# SH5_-_MICROCONTROLLER.net
KiCad netlist of a schematic drawn in Altium Designer
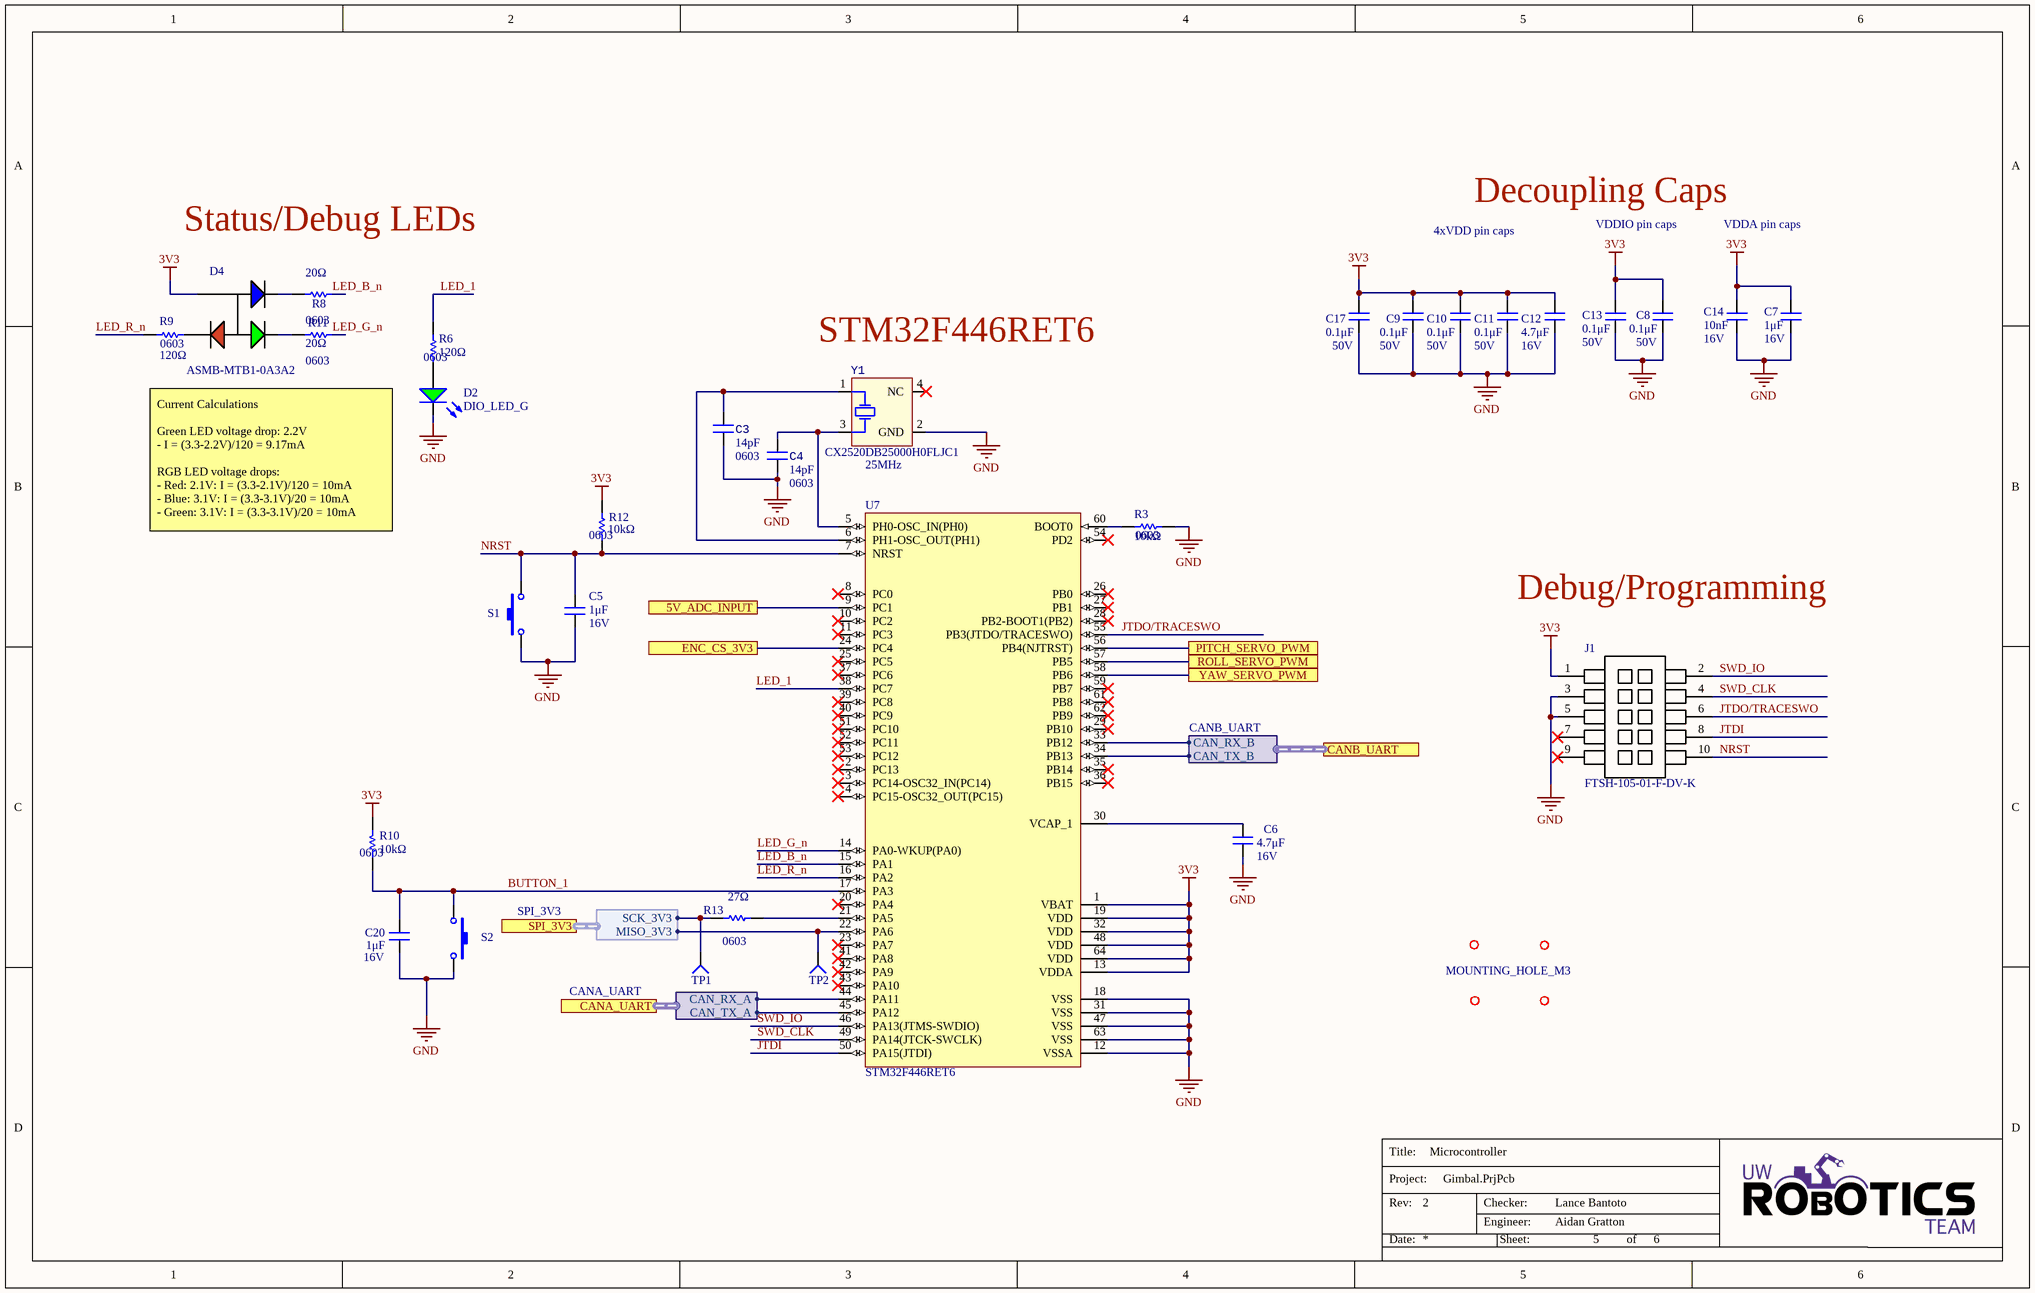
[diagram p0: SH5 - MICROCONTROLLER.SchDoc]

(export (version "E")
  (design (tool "Eeschema 10.0.6"))
  (components
    (comp (ref "C3")
      (value "14pF")
      (footprint "CAP0603")
      (description "CAP CER 14PF 50V C0G/NP0 0603")
      (fields (field (name "PACKAGE/FOOTPRINT") "0603") (field (name "Comment") "CAP_14pF_50V_0603"))
      (libsource (lib "UWRT_Schematic_Library_2020") (part "CAP_14pF_50V_0603"))
    )
    (comp (ref "C4")
      (value "14pF")
      (footprint "CAP0603")
      (description "CAP CER 14PF 50V C0G/NP0 0603")
      (fields (field (name "PACKAGE/FOOTPRINT") "0603") (field (name "Comment") "CAP_14pF_50V_0603"))
      (libsource (lib "UWRT_Schematic_Library_2020") (part "CAP_14pF_50V_0603"))
    )
    (comp (ref "C5")
      (value "1μF")
      (footprint "CAP2012")
      (description "CAP CER 1UF 16V X7R 0805")
      (fields
        (field (name "TOLERANCE") "10%")
        (field (name "VOLTAGE RATING") "16V")
        (field (name "Comment") "CAP_1uF_16V_0805")
      )
      (libsource (lib "UWRT_Schematic_Library_2020") (part "CAP_1uF_16V_0805"))
    )
    (comp (ref "C6")
      (value "4.7μF")
      (footprint "CAP2012")
      (description "CAP CER 4.7UF 16V X5R 0805")
      (fields
        (field (name "VOLTAGE RATING") "16V")
        (field (name "LCSC PART #") "C1779")
        (field (name "Comment") "CAP_4.7uF_16V_0805")
      )
      (libsource (lib "UWRT_Schematic_Library_2020") (part "CAP_4.7uF_16V_0805"))
    )
    (comp (ref "C7")
      (value "1μF")
      (footprint "CAP0603")
      (description "CAP CER 1UF 16V Y5V 0603")
      (fields
        (field (name "VOLTAGE RATING") "16V")
        (field (name "MANUFACTURER PART NUMBER") "CC0603ZRY5V7BB105")
        (field (name "Comment") "CAP_1uF_16V_0603")
      )
      (libsource (lib "UWRT_Schematic_Library_2020") (part "CAP_1uF_16V_0603"))
    )
    (comp (ref "C8")
      (value "0.1μF")
      (footprint "CAP0603")
      (description "CAP CER 0.1UF 50V X7R 0603")
      (fields (field (name "VOLTAGE RATING") "50V") (field (name "Comment") "CAP_0.1uF_50V_0603"))
      (libsource (lib "UWRT_Schematic_Library_2020") (part "CAP_0.1uF_50V_0603"))
    )
    (comp (ref "C9")
      (value "0.1μF")
      (footprint "CAP0603")
      (description "CAP CER 0.1UF 50V X7R 0603")
      (fields (field (name "VOLTAGE RATING") "50V") (field (name "Comment") "CAP_0.1uF_50V_0603"))
      (libsource (lib "UWRT_Schematic_Library_2020") (part "CAP_0.1uF_50V_0603"))
    )
    (comp (ref "C10")
      (value "0.1μF")
      (footprint "CAP0603")
      (description "CAP CER 0.1UF 50V X7R 0603")
      (fields (field (name "VOLTAGE RATING") "50V") (field (name "Comment") "CAP_0.1uF_50V_0603"))
      (libsource (lib "UWRT_Schematic_Library_2020") (part "CAP_0.1uF_50V_0603"))
    )
    (comp (ref "C11")
      (value "0.1μF")
      (footprint "CAP0603")
      (description "CAP CER 0.1UF 50V X7R 0603")
      (fields (field (name "VOLTAGE RATING") "50V") (field (name "Comment") "CAP_0.1uF_50V_0603"))
      (libsource (lib "UWRT_Schematic_Library_2020") (part "CAP_0.1uF_50V_0603"))
    )
    (comp (ref "C12")
      (value "4.7μF")
      (footprint "CAP2012")
      (description "CAP CER 4.7UF 16V X5R 0805")
      (fields
        (field (name "VOLTAGE RATING") "16V")
        (field (name "LCSC PART #") "C1779")
        (field (name "Comment") "CAP_4.7uF_16V_0805")
      )
      (libsource (lib "UWRT_Schematic_Library_2020") (part "CAP_4.7uF_16V_0805"))
    )
    (comp (ref "C13")
      (value "0.1μF")
      (footprint "CAP0603")
      (description "CAP CER 0.1UF 50V X7R 0603")
      (fields (field (name "VOLTAGE RATING") "50V") (field (name "Comment") "CAP_0.1uF_50V_0603"))
      (libsource (lib "UWRT_Schematic_Library_2020") (part "CAP_0.1uF_50V_0603"))
    )
    (comp (ref "C14")
      (value "10nF")
      (footprint "CAP0603")
      (description "CAP CER 10000PF 16V X7R 0603")
      (fields (field (name "VOLTAGE RATING") "16V") (field (name "Comment") "CAP_10nF_0603"))
      (libsource (lib "UWRT_Schematic_Library_2020") (part "CAP_10nF_0603"))
    )
    (comp (ref "C17")
      (value "0.1μF")
      (footprint "CAP0603")
      (description "CAP CER 0.1UF 50V X7R 0603")
      (fields (field (name "VOLTAGE RATING") "50V") (field (name "Comment") "CAP_0.1uF_50V_0603"))
      (libsource (lib "UWRT_Schematic_Library_2020") (part "CAP_0.1uF_50V_0603"))
    )
    (comp (ref "C20")
      (value "1μF")
      (footprint "CAP2012")
      (description "CAP CER 1UF 16V X7R 0805")
      (fields
        (field (name "TOLERANCE") "10%")
        (field (name "VOLTAGE RATING") "16V")
        (field (name "Comment") "CAP_1uF_16V_0805")
      )
      (libsource (lib "UWRT_Schematic_Library_2020") (part "CAP_1uF_16V_0805"))
    )
    (comp (ref "D2")
      (value "DIO_LED_G")
      (footprint "LED_0805_GREEN")
      (description "LED GREEN DIFFUSED 0805 SMD")
      (libsource (lib "UWRT_Schematic_Library_2020") (part "DIO_LED_G"))
    )
    (comp (ref "D4")
      (value "LED_RGB")
      (footprint "LED_RGB")
      (description "LED RGB DIFFUSED 4PLCC SMD")
      (fields (field (name "MANUFACTURER PART NUMBER 1") "ASMB-MTB1-0A3A2"))
      (libsource (lib "UWRT_Schematic_Library_2020") (part "LED_RGB"))
    )
    (comp (ref "J1")
      (value "CON_PROGRAMMING")
      (footprint "FTSH-105-01-F-DV-K-P-TR")
      (description "CONN HEADER SMD 10POS 1.27MM")
      (fields (field (name "MANUFACTURER PART NUMBER 1") "FTSH-105-01-F-DV-K"))
      (libsource (lib "UWRT_Schematic_Library_2020") (part "CON_PROGRAMMING"))
    )
    (comp (ref "MH1")
      (value "MOUNTING_HOLE_M3")
      (footprint "MOUNTING_HOLE_3mm_GIMBAL_REV2")
      (description "MOUNTING_HOLE_M3 Gimbal Rev2")
      (libsource (lib "UWRT_Schematic_Library_2020") (part "MOUNTING_HOLE_M3_GIMBAL_REV2"))
    )
    (comp (ref "MH2")
      (value "MOUNTING_HOLE_M3")
      (footprint "MOUNTING_HOLE_3mm_GIMBAL_REV2")
      (description "MOUNTING_HOLE_M3 Gimbal Rev2")
      (libsource (lib "UWRT_Schematic_Library_2020") (part "MOUNTING_HOLE_M3_GIMBAL_REV2"))
    )
    (comp (ref "MH3")
      (value "MOUNTING_HOLE_M3")
      (footprint "MOUNTING_HOLE_3mm_GIMBAL_REV2")
      (description "MOUNTING_HOLE_M3 Gimbal Rev2")
      (libsource (lib "UWRT_Schematic_Library_2020") (part "MOUNTING_HOLE_M3_GIMBAL_REV2"))
    )
    (comp (ref "MH4")
      (value "MOUNTING_HOLE_M3")
      (footprint "MOUNTING_HOLE_3mm_GIMBAL_REV2")
      (description "MOUNTING_HOLE_M3 Gimbal Rev2")
      (libsource (lib "UWRT_Schematic_Library_2020") (part "MOUNTING_HOLE_M3_GIMBAL_REV2"))
    )
    (comp (ref "R3")
      (value "10kΩ")
      (footprint "RESC0603")
      (description "RES 10K OHM 5% 1/10W 0603")
      (fields
        (field (name "TOLERANCE") "5%")
        (field (name "PACKAGE/FOOTPRINT") "0603")
        (field (name "Comment") "RES_10kΩ_0603_5%")
      )
      (libsource (lib "UWRT_Schematic_Library_2020") (part "RES_10kΩ_0603_5%"))
    )
    (comp (ref "R6")
      (value "120Ω")
      (footprint "RESC0603")
      (description "RES 120 OHM 5% 1/10W 0603")
      (fields (field (name "PACKAGE/FOOTPRINT") "0603") (field (name "Comment") "RES_120Ω_0603"))
      (libsource (lib "UWRT_Schematic_Library_2020") (part "RES_120Ω_0603_5%"))
    )
    (comp (ref "R8")
      (value "20Ω")
      (footprint "RESC0603")
      (description "RES 20 OHM 5% 1/10W 0603")
      (fields
        (field (name "TOLERANCE") "5%")
        (field (name "PACKAGE/FOOTPRINT") "0603")
        (field (name "Comment") "RES_20Ω_0603_5%")
      )
      (libsource (lib "UWRT_Schematic_Library_2020") (part "RES_20Ω_0603_5%"))
    )
    (comp (ref "R9")
      (value "120Ω")
      (footprint "RESC0603")
      (description "RES 120 OHM 5% 1/10W 0603")
      (fields (field (name "PACKAGE/FOOTPRINT") "0603") (field (name "Comment") "RES_120Ω_0603"))
      (libsource (lib "UWRT_Schematic_Library_2020") (part "RES_120Ω_0603_5%"))
    )
    (comp (ref "R10")
      (value "10kΩ")
      (footprint "RESC0603")
      (description "RES 10K OHM 5% 1/10W 0603")
      (fields
        (field (name "TOLERANCE") "5%")
        (field (name "PACKAGE/FOOTPRINT") "0603")
        (field (name "Comment") "RES_10kΩ_0603_5%")
      )
      (libsource (lib "UWRT_Schematic_Library_2020") (part "RES_10kΩ_0603_5%"))
    )
    (comp (ref "R11")
      (value "20Ω")
      (footprint "RESC0603")
      (description "RES 20 OHM 5% 1/10W 0603")
      (fields
        (field (name "TOLERANCE") "5%")
        (field (name "PACKAGE/FOOTPRINT") "0603")
        (field (name "Comment") "RES_20Ω_0603_5%")
      )
      (libsource (lib "UWRT_Schematic_Library_2020") (part "RES_20Ω_0603_5%"))
    )
    (comp (ref "R12")
      (value "10kΩ")
      (footprint "RESC0603")
      (description "RES 10K OHM 5% 1/10W 0603")
      (fields
        (field (name "TOLERANCE") "5%")
        (field (name "PACKAGE/FOOTPRINT") "0603")
        (field (name "Comment") "RES_10kΩ_0603_5%")
      )
      (libsource (lib "UWRT_Schematic_Library_2020") (part "RES_10kΩ_0603_5%"))
    )
    (comp (ref "R13")
      (value "RES_27Ω_0603_5%")
      (footprint "RESC0603")
      (description "RES 27 OHM 5% 1/10W 0603")
      (fields
        (field (name "TOLERANCE") "5%")
        (field (name "RESISTANCE") "27Ω")
        (field (name "PACKAGE/FOOTPRINT") "0603")
      )
      (libsource (lib "UWRT_Schematic_Library_2020") (part "RES_27Ω_0603_5%"))
    )
    (comp (ref "S1")
      (value "SW_TACTILE")
      (footprint "B3U-1000P")
      (description "SWITCH TACTILE SPST-NO 0.05A 12V")
      (libsource (lib "UWRT_Schematic_Library_2020") (part "SW_TACTILE"))
    )
    (comp (ref "S2")
      (value "SW_TACTILE")
      (footprint "B3U-1000P")
      (description "SWITCH TACTILE SPST-NO 0.05A 12V")
      (libsource (lib "UWRT_Schematic_Library_2020") (part "SW_TACTILE"))
    )
    (comp (ref "TP1")
      (value "TESTPOINT_1MM_CIRCLE")
      (footprint "TESTPOINT_CIRCLE_1MM")
      (description "TESTPOINT 1MM CIRCLE")
      (libsource (lib "UWRT_Schematic_Library_2020") (part "TESTPOINT_1MM_CIRCLE"))
    )
    (comp (ref "TP2")
      (value "TESTPOINT_1MM_CIRCLE")
      (footprint "TESTPOINT_CIRCLE_1MM")
      (description "TESTPOINT 1MM CIRCLE")
      (libsource (lib "UWRT_Schematic_Library_2020") (part "TESTPOINT_1MM_CIRCLE"))
    )
    (comp (ref "U7")
      (value "STM32F446RET6")
      (footprint "STM-LQFP64_L")
      (libsource (lib "UWRT_Schematic_Library_2020") (part "MCU_STM32F446RET6"))
    )
    (comp (ref "Y1")
      (value "CRYSTAL_25MHZ")
      (footprint "SOIC254P1016X440-4N")
      (description "CRYSTAL 25.0000MHZ 12PF SMD")
      (fields
        (field (name "MANUFACTURER PART NUMBER 1") "CX2520DB25000H0FLJC1")
        (field (name "FREQUENCY") "25MHz")
      )
      (libsource (lib "UWRT_Schematic_Library_2020") (part "CRYSTAL_25MHZ"))
    )
  )
  (nets
    (net (code "4") (name "/5V_ADC_INPUT") (class "Default")
      (node (ref "U7") (pin "9") (pinfunction "PC1_9") (pintype "bidirectional"))
    )
    (net (code "5") (name "/BUTTON_1") (class "Default")
      (node (ref "C20") (pin "2") (pinfunction "2_2") (pintype "passive"))
      (node (ref "R10") (pin "2") (pinfunction "2_2") (pintype "passive"))
      (node (ref "S2") (pin "2") (pinfunction "2_2") (pintype "passive"))
      (node (ref "U7") (pin "17") (pinfunction "PA3_17") (pintype "bidirectional"))
    )
    (net (code "6") (name "/CAN_RX_A") (class "Default")
      (node (ref "U7") (pin "44") (pinfunction "PA11_44") (pintype "bidirectional"))
    )
    (net (code "7") (name "/CAN_RX_B") (class "Default")
      (node (ref "U7") (pin "33") (pinfunction "PB12_33") (pintype "bidirectional"))
    )
    (net (code "8") (name "/CAN_TX_A") (class "Default")
      (node (ref "U7") (pin "45") (pinfunction "PA12_45") (pintype "bidirectional"))
    )
    (net (code "9") (name "/CAN_TX_B") (class "Default")
      (node (ref "U7") (pin "34") (pinfunction "PB13_34") (pintype "bidirectional"))
    )
    (net (code "10") (name "/ENC_CS_3V3") (class "Default")
      (node (ref "U7") (pin "24") (pinfunction "PC4_24") (pintype "bidirectional"))
    )
    (net (code "11") (name "/JTDI") (class "Default")
      (node (ref "J1") (pin "8") (pinfunction "8_8") (pintype "passive"))
      (node (ref "U7") (pin "50") (pinfunction "PA15(JTDI)_50") (pintype "bidirectional"))
    )
    (net (code "12") (name "/JTDO{slash}TRACESWO") (class "Default")
      (node (ref "J1") (pin "6") (pinfunction "6_6") (pintype "passive"))
      (node (ref "U7") (pin "55") (pinfunction "PB3(JTDO/TRACESWO)_55") (pintype "bidirectional"))
    )
    (net (code "13") (name "/LED_1") (class "Default")
      (node (ref "R6") (pin "1") (pinfunction "1_1") (pintype "passive"))
      (node (ref "U7") (pin "38") (pinfunction "PC7_38") (pintype "bidirectional"))
    )
    (net (code "14") (name "/LED_B_n") (class "Default")
      (node (ref "R8") (pin "2") (pinfunction "2_2") (pintype "passive"))
      (node (ref "U7") (pin "15") (pinfunction "PA1_15") (pintype "bidirectional"))
    )
    (net (code "15") (name "/LED_G_n") (class "Default")
      (node (ref "R11") (pin "2") (pinfunction "2_2") (pintype "passive"))
      (node (ref "U7") (pin "14") (pinfunction "PA0-WKUP(PA0)_14") (pintype "bidirectional"))
    )
    (net (code "16") (name "/LED_R_n") (class "Default")
      (node (ref "R9") (pin "1") (pinfunction "1_1") (pintype "passive"))
      (node (ref "U7") (pin "16") (pinfunction "PA2_16") (pintype "bidirectional"))
    )
    (net (code "17") (name "/MISO_3V3") (class "Default")
      (node (ref "TP2") (pin "1") (pinfunction "=value_1") (pintype "passive"))
      (node (ref "U7") (pin "22") (pinfunction "PA6_22") (pintype "bidirectional"))
    )
    (net (code "18") (name "/NRST") (class "Default")
      (node (ref "C5") (pin "2") (pinfunction "2_2") (pintype "passive"))
      (node (ref "J1") (pin "10") (pinfunction "10_10") (pintype "passive"))
      (node (ref "R12") (pin "1") (pinfunction "1_1") (pintype "passive"))
      (node (ref "S1") (pin "2") (pinfunction "2_2") (pintype "passive"))
      (node (ref "U7") (pin "7") (pinfunction "NRST_7") (pintype "bidirectional"))
    )
    (net (code "19") (name "/PITCH_SERVO_PWM") (class "Default")
      (node (ref "U7") (pin "56") (pinfunction "PB4(NJTRST)_56") (pintype "bidirectional"))
    )
    (net (code "20") (name "/ROLL_SERVO_PWM") (class "Default")
      (node (ref "U7") (pin "57") (pinfunction "PB5_57") (pintype "bidirectional"))
    )
    (net (code "21") (name "/SCK_3V3") (class "Default")
      (node (ref "R13") (pin "1") (pinfunction "1_1") (pintype "passive"))
      (node (ref "TP1") (pin "1") (pinfunction "=value_1") (pintype "passive"))
    )
    (net (code "22") (name "/SWD_CLK") (class "Default")
      (node (ref "J1") (pin "4") (pinfunction "4_4") (pintype "passive"))
      (node (ref "U7") (pin "49") (pinfunction "PA14(JTCK-SWCLK)_49") (pintype "bidirectional"))
    )
    (net (code "23") (name "/SWD_IO") (class "Default")
      (node (ref "J1") (pin "2") (pinfunction "2_2") (pintype "passive"))
      (node (ref "U7") (pin "46") (pinfunction "PA13(JTMS-SWDIO)_46") (pintype "bidirectional"))
    )
    (net (code "24") (name "/YAW_SERVO_PWM") (class "Default")
      (node (ref "U7") (pin "58") (pinfunction "PB6_58") (pintype "bidirectional"))
    )
    (net (code "28") (name "3V3") (class "Default")
      (node (ref "C10") (pin "2") (pinfunction "2_2") (pintype "passive"))
      (node (ref "C11") (pin "2") (pinfunction "2_2") (pintype "passive"))
      (node (ref "C12") (pin "2") (pinfunction "2_2") (pintype "passive"))
      (node (ref "C13") (pin "2") (pinfunction "2_2") (pintype "passive"))
      (node (ref "C14") (pin "2") (pinfunction "2_2") (pintype "passive"))
      (node (ref "C17") (pin "2") (pinfunction "2_2") (pintype "passive"))
      (node (ref "C7") (pin "2") (pinfunction "2_2") (pintype "passive"))
      (node (ref "C8") (pin "2") (pinfunction "2_2") (pintype "passive"))
      (node (ref "C9") (pin "2") (pinfunction "2_2") (pintype "passive"))
      (node (ref "D4") (pin "4") (pinfunction "COMMON_ANODE_4") (pintype "passive"))
      (node (ref "J1") (pin "1") (pinfunction "1_1") (pintype "passive"))
      (node (ref "R10") (pin "1") (pinfunction "1_1") (pintype "passive"))
      (node (ref "R12") (pin "2") (pinfunction "2_2") (pintype "passive"))
      (node (ref "U7") (pin "1") (pinfunction "VBAT_1") (pintype "power_in"))
      (node (ref "U7") (pin "13") (pinfunction "VDDA_13") (pintype "power_in"))
      (node (ref "U7") (pin "19") (pinfunction "VDD_19") (pintype "power_in"))
      (node (ref "U7") (pin "32") (pinfunction "VDD_32") (pintype "power_in"))
      (node (ref "U7") (pin "48") (pinfunction "VDD_48") (pintype "power_in"))
      (node (ref "U7") (pin "64") (pinfunction "VDD_64") (pintype "power_in"))
    )
    (net (code "29") (name "GND") (class "Default")
      (node (ref "C10") (pin "1") (pinfunction "1_1") (pintype "passive"))
      (node (ref "C11") (pin "1") (pinfunction "1_1") (pintype "passive"))
      (node (ref "C12") (pin "1") (pinfunction "1_1") (pintype "passive"))
      (node (ref "C13") (pin "1") (pinfunction "1_1") (pintype "passive"))
      (node (ref "C14") (pin "1") (pinfunction "1_1") (pintype "passive"))
      (node (ref "C17") (pin "1") (pinfunction "1_1") (pintype "passive"))
      (node (ref "C20") (pin "1") (pinfunction "1_1") (pintype "passive"))
      (node (ref "C3") (pin "1") (pinfunction "1_1") (pintype "passive"))
      (node (ref "C4") (pin "1") (pinfunction "1_1") (pintype "passive"))
      (node (ref "C5") (pin "1") (pinfunction "1_1") (pintype "passive"))
      (node (ref "C6") (pin "1") (pinfunction "1_1") (pintype "passive"))
      (node (ref "C7") (pin "1") (pinfunction "1_1") (pintype "passive"))
      (node (ref "C8") (pin "1") (pinfunction "1_1") (pintype "passive"))
      (node (ref "C9") (pin "1") (pinfunction "1_1") (pintype "passive"))
      (node (ref "D2") (pin "2") (pinfunction "K_2") (pintype "passive"))
      (node (ref "J1") (pin "3") (pinfunction "3_3") (pintype "passive"))
      (node (ref "J1") (pin "5") (pinfunction "5_5") (pintype "passive"))
      (node (ref "R3") (pin "2") (pinfunction "2_2") (pintype "passive"))
      (node (ref "S1") (pin "1") (pinfunction "1_1") (pintype "passive"))
      (node (ref "S2") (pin "1") (pinfunction "1_1") (pintype "passive"))
      (node (ref "U7") (pin "12") (pinfunction "VSSA_12") (pintype "power_in"))
      (node (ref "U7") (pin "18") (pinfunction "VSS_18") (pintype "power_in"))
      (node (ref "U7") (pin "31") (pinfunction "VSS_31") (pintype "power_in"))
      (node (ref "U7") (pin "47") (pinfunction "VSS_47") (pintype "power_in"))
      (node (ref "U7") (pin "63") (pinfunction "VSS_63") (pintype "power_in"))
      (node (ref "Y1") (pin "2") (pinfunction "GND_2") (pintype "power_in"))
    )
    (net (code "30") (name "Net-(D2-A)") (class "Default")
      (node (ref "D2") (pin "1") (pinfunction "A_1") (pintype "passive"))
      (node (ref "R6") (pin "2") (pinfunction "2_2") (pintype "passive"))
    )
    (net (code "31") (name "Net-(D4-CATHODE_(BLUE))") (class "Default")
      (node (ref "D4") (pin "3") (pinfunction "CATHODE_(BLUE)_3") (pintype "passive"))
      (node (ref "R8") (pin "1") (pinfunction "1_1") (pintype "passive"))
    )
    (net (code "32") (name "Net-(D4-CATHODE_(GREEN))") (class "Default")
      (node (ref "D4") (pin "2") (pinfunction "CATHODE_(GREEN)_2") (pintype "passive"))
      (node (ref "R11") (pin "1") (pinfunction "1_1") (pintype "passive"))
    )
    (net (code "33") (name "Net-(D4-CATHODE_(RED))") (class "Default")
      (node (ref "D4") (pin "1") (pinfunction "CATHODE_(RED)_1") (pintype "passive"))
      (node (ref "R9") (pin "2") (pinfunction "2_2") (pintype "passive"))
    )
    (net (code "34") (name "Net-(U7-BOOT0)") (class "Default")
      (node (ref "R3") (pin "1") (pinfunction "1_1") (pintype "passive"))
      (node (ref "U7") (pin "60") (pinfunction "BOOT0_60") (pintype "input"))
    )
    (net (code "35") (name "Net-(U7-PA5)") (class "Default")
      (node (ref "R13") (pin "2") (pinfunction "2_2") (pintype "passive"))
      (node (ref "U7") (pin "21") (pinfunction "PA5_21") (pintype "bidirectional"))
    )
    (net (code "36") (name "Net-(U7-PH0-OSC_IN(PH0))") (class "Default")
      (node (ref "C4") (pin "2") (pinfunction "2_2") (pintype "passive"))
      (node (ref "U7") (pin "5") (pinfunction "PH0-OSC_IN(PH0)_5") (pintype "bidirectional"))
      (node (ref "Y1") (pin "3") (pinfunction "HOT_3") (pintype "passive"))
    )
    (net (code "37") (name "Net-(U7-PH1-OSC_OUT(PH1))") (class "Default")
      (node (ref "C3") (pin "2") (pinfunction "2_2") (pintype "passive"))
      (node (ref "U7") (pin "6") (pinfunction "PH1-OSC_OUT(PH1)_6") (pintype "bidirectional"))
      (node (ref "Y1") (pin "1") (pinfunction "HOT_1") (pintype "passive"))
    )
    (net (code "38") (name "Net-(U7-VCAP_1)") (class "Default")
      (node (ref "C6") (pin "2") (pinfunction "2_2") (pintype "passive"))
      (node (ref "U7") (pin "30") (pinfunction "VCAP_1_30") (pintype "passive"))
    )
    (net (code "39") (name "unconnected-(J1-Pad7)") (class "Default")
      (node (ref "J1") (pin "7") (pinfunction "7_7") (pintype "passive+no_connect"))
    )
    (net (code "40") (name "unconnected-(J1-Pad9)") (class "Default")
      (node (ref "J1") (pin "9") (pinfunction "9_9") (pintype "passive+no_connect"))
    )
    (net (code "41") (name "unconnected-(U7-PA4-Pad20)") (class "Default")
      (node (ref "U7") (pin "20") (pinfunction "PA4_20") (pintype "bidirectional+no_connect"))
    )
    (net (code "42") (name "unconnected-(U7-PA7-Pad23)") (class "Default")
      (node (ref "U7") (pin "23") (pinfunction "PA7_23") (pintype "bidirectional+no_connect"))
    )
    (net (code "43") (name "unconnected-(U7-PA8-Pad41)") (class "Default")
      (node (ref "U7") (pin "41") (pinfunction "PA8_41") (pintype "bidirectional+no_connect"))
    )
    (net (code "44") (name "unconnected-(U7-PA9-Pad42)") (class "Default")
      (node (ref "U7") (pin "42") (pinfunction "PA9_42") (pintype "bidirectional+no_connect"))
    )
    (net (code "45") (name "unconnected-(U7-PA10-Pad43)") (class "Default")
      (node (ref "U7") (pin "43") (pinfunction "PA10_43") (pintype "bidirectional+no_connect"))
    )
    (net (code "46") (name "unconnected-(U7-PB0-Pad26)") (class "Default")
      (node (ref "U7") (pin "26") (pinfunction "PB0_26") (pintype "bidirectional+no_connect"))
    )
    (net (code "47") (name "unconnected-(U7-PB1-Pad27)") (class "Default")
      (node (ref "U7") (pin "27") (pinfunction "PB1_27") (pintype "bidirectional+no_connect"))
    )
    (net (code "48") (name "unconnected-(U7-PB2-BOOT1(PB2)-Pad28)") (class "Default")
      (node (ref "U7") (pin "28") (pinfunction "PB2-BOOT1(PB2)_28") (pintype "bidirectional+no_connect"))
    )
    (net (code "49") (name "unconnected-(U7-PB7-Pad59)") (class "Default")
      (node (ref "U7") (pin "59") (pinfunction "PB7_59") (pintype "bidirectional+no_connect"))
    )
    (net (code "50") (name "unconnected-(U7-PB8-Pad61)") (class "Default")
      (node (ref "U7") (pin "61") (pinfunction "PB8_61") (pintype "bidirectional+no_connect"))
    )
    (net (code "51") (name "unconnected-(U7-PB9-Pad62)") (class "Default")
      (node (ref "U7") (pin "62") (pinfunction "PB9_62") (pintype "bidirectional+no_connect"))
    )
    (net (code "52") (name "unconnected-(U7-PB10-Pad29)") (class "Default")
      (node (ref "U7") (pin "29") (pinfunction "PB10_29") (pintype "bidirectional+no_connect"))
    )
    (net (code "53") (name "unconnected-(U7-PB14-Pad35)") (class "Default")
      (node (ref "U7") (pin "35") (pinfunction "PB14_35") (pintype "bidirectional+no_connect"))
    )
    (net (code "54") (name "unconnected-(U7-PB15-Pad36)") (class "Default")
      (node (ref "U7") (pin "36") (pinfunction "PB15_36") (pintype "bidirectional+no_connect"))
    )
    (net (code "55") (name "unconnected-(U7-PC0-Pad8)") (class "Default")
      (node (ref "U7") (pin "8") (pinfunction "PC0_8") (pintype "bidirectional+no_connect"))
    )
    (net (code "56") (name "unconnected-(U7-PC2-Pad10)") (class "Default")
      (node (ref "U7") (pin "10") (pinfunction "PC2_10") (pintype "bidirectional+no_connect"))
    )
    (net (code "57") (name "unconnected-(U7-PC3-Pad11)") (class "Default")
      (node (ref "U7") (pin "11") (pinfunction "PC3_11") (pintype "bidirectional+no_connect"))
    )
    (net (code "58") (name "unconnected-(U7-PC5-Pad25)") (class "Default")
      (node (ref "U7") (pin "25") (pinfunction "PC5_25") (pintype "bidirectional+no_connect"))
    )
    (net (code "59") (name "unconnected-(U7-PC6-Pad37)") (class "Default")
      (node (ref "U7") (pin "37") (pinfunction "PC6_37") (pintype "bidirectional+no_connect"))
    )
    (net (code "60") (name "unconnected-(U7-PC8-Pad39)") (class "Default")
      (node (ref "U7") (pin "39") (pinfunction "PC8_39") (pintype "bidirectional+no_connect"))
    )
    (net (code "61") (name "unconnected-(U7-PC9-Pad40)") (class "Default")
      (node (ref "U7") (pin "40") (pinfunction "PC9_40") (pintype "bidirectional+no_connect"))
    )
    (net (code "62") (name "unconnected-(U7-PC10-Pad51)") (class "Default")
      (node (ref "U7") (pin "51") (pinfunction "PC10_51") (pintype "bidirectional+no_connect"))
    )
    (net (code "63") (name "unconnected-(U7-PC11-Pad52)") (class "Default")
      (node (ref "U7") (pin "52") (pinfunction "PC11_52") (pintype "bidirectional+no_connect"))
    )
    (net (code "64") (name "unconnected-(U7-PC12-Pad53)") (class "Default")
      (node (ref "U7") (pin "53") (pinfunction "PC12_53") (pintype "bidirectional+no_connect"))
    )
    (net (code "65") (name "unconnected-(U7-PC13-Pad2)") (class "Default")
      (node (ref "U7") (pin "2") (pinfunction "PC13_2") (pintype "bidirectional+no_connect"))
    )
    (net (code "66") (name "unconnected-(U7-PC14-OSC32_IN(PC14)-Pad3)") (class "Default")
      (node (ref "U7") (pin "3") (pinfunction "PC14-OSC32_IN(PC14)_3") (pintype "bidirectional+no_connect"))
    )
    (net (code "67") (name "unconnected-(U7-PC15-OSC32_OUT(PC15)-Pad4)") (class "Default")
      (node (ref "U7") (pin "4") (pinfunction "PC15-OSC32_OUT(PC15)_4") (pintype "bidirectional+no_connect"))
    )
    (net (code "68") (name "unconnected-(U7-PD2-Pad54)") (class "Default")
      (node (ref "U7") (pin "54") (pinfunction "PD2_54") (pintype "bidirectional+no_connect"))
    )
    (net (code "69") (name "unconnected-(Y1-NC-Pad4)") (class "Default")
      (node (ref "Y1") (pin "4") (pinfunction "NC_4") (pintype "passive+no_connect"))
    )
  )
)
